# Shield_Amir_EDO_V_0_2.net
KiCad netlist of a schematic drawn in EasyEDA
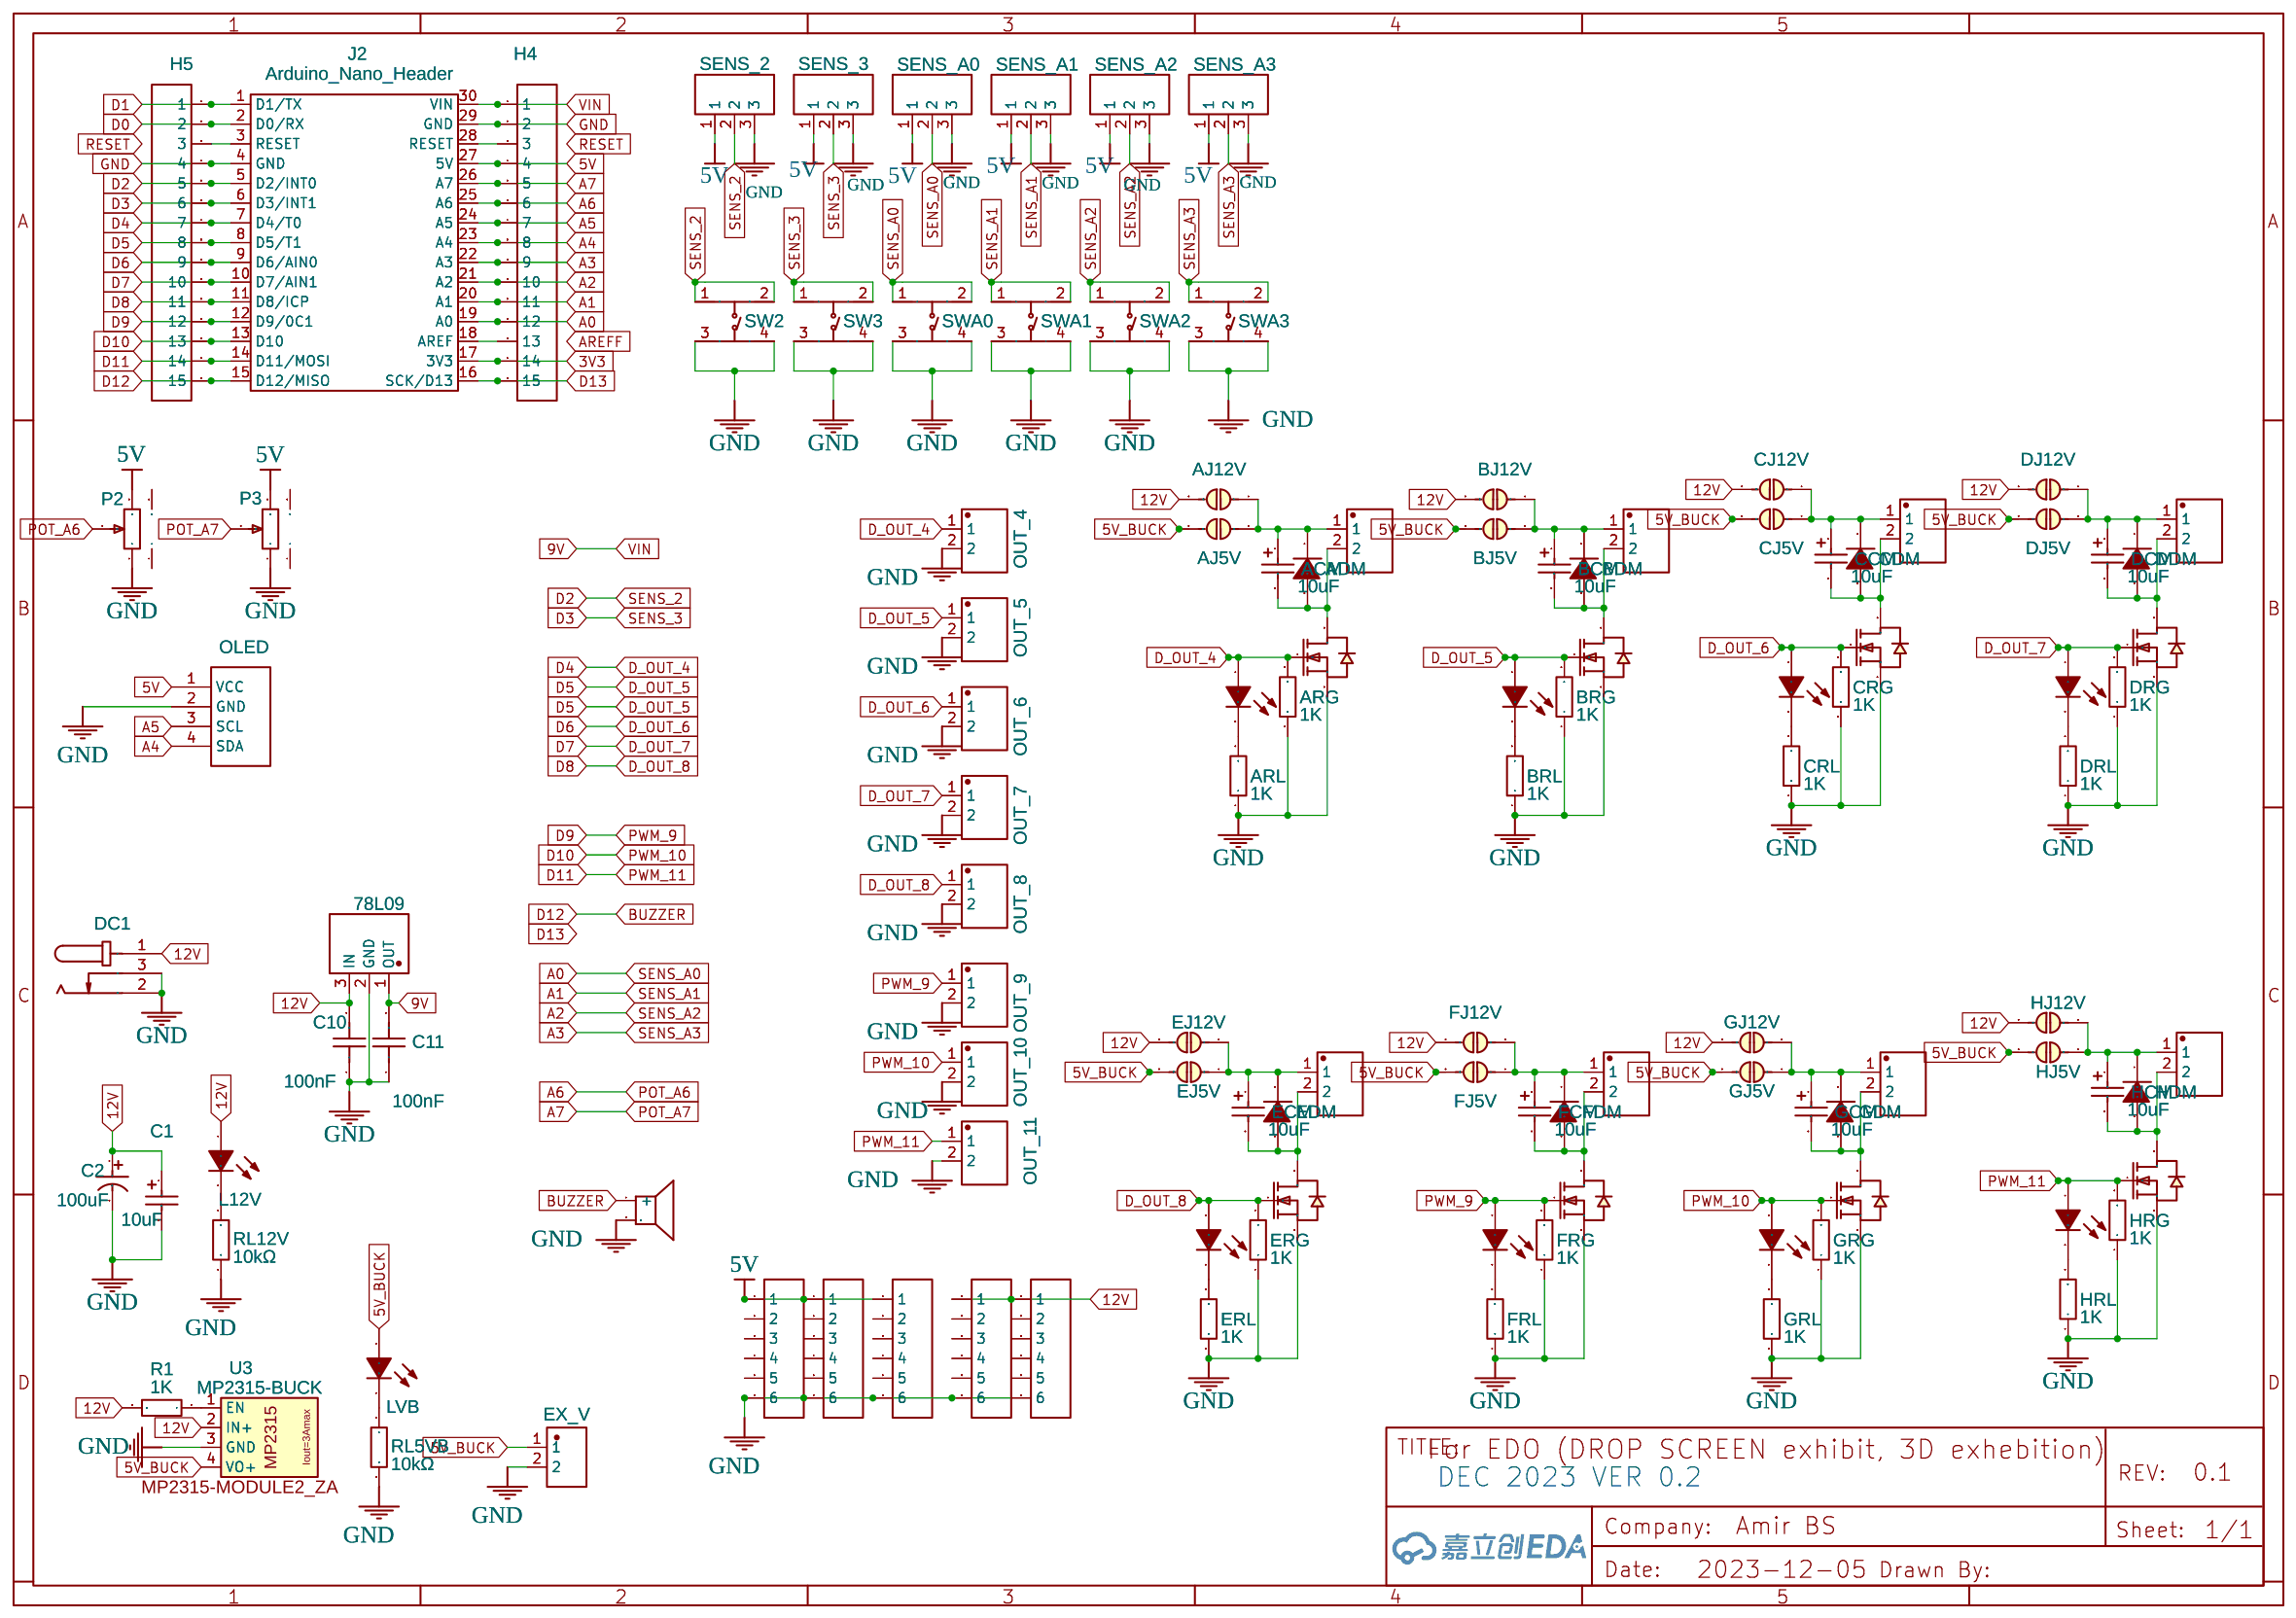
[diagram p0: schematic sheet]

(export (version "E")
  (design (tool "Eeschema 10.0.6"))
  (components
    (comp (ref "ACM")
      (value "10uF")
      (fields (field (name "Manufacturer Part") "TAJA106K016RNJ") (field (name "Manufacturer") "Kyocera AVX"))
      (libsource (lib "") (part "TAJA106K016RNJ_5"))
    )
    (comp (ref "ACON")
      (value "KF2510-2A")
      (fields (field (name "BOM_Supplier Part") "C27543"))
      (libsource (lib "") (part "KF2510-2A_6"))
    )
    (comp (ref "ADM")
      (value "1N4007")
      (fields (field (name "BOM_Manufacturer Part") "1N4007F") (field (name "BOM_Supplier Part") "C110856"))
      (libsource (lib "") (part "1N4007F_5"))
    )
    (comp (ref "AJ5V") (value "JUMPER-SMT_2") (libsource (lib "") (part "JUMPER-SMT_2_7")))
    (comp (ref "AJ12V") (value "JUMPER-SMT_2") (libsource (lib "") (part "JUMPER-SMT_2_3")))
    (comp (ref "ALD")
      (value "LED")
      (fields
        (field (name "BOM_Manufacturer Part") "19-217/BHC-ZL1M2RY/3T")
        (field (name "BOM_Supplier Part") "C72041")
      )
      (libsource (lib "") (part "19-217/BHC-ZL1M2RY/3T_4"))
    )
    (comp (ref "AQ")
      (value "Q")
      (fields (field (name "BOM_Manufacturer Part") "AO3400") (field (name "BOM_Supplier Part") "C5224189"))
      (libsource (lib "") (part "JSM2302_1"))
    )
    (comp (ref "ARG")
      (value "1K")
      (fields
        (field (name "BOM_Manufacturer Part") "0603WAF1001T5E")
        (field (name "BOM_Supplier Part") "C21190")
      )
      (libsource (lib "") (part "0603WAF1001T5E_11"))
    )
    (comp (ref "ARL")
      (value "1K")
      (fields
        (field (name "BOM_Manufacturer Part") "0603WAF1001T5E")
        (field (name "BOM_Supplier Part") "C21190")
      )
      (libsource (lib "") (part "0603WAF1001T5E_5"))
    )
    (comp (ref "BCM")
      (value "10uF")
      (fields (field (name "Manufacturer Part") "TAJA106K016RNJ") (field (name "Manufacturer") "Kyocera AVX"))
      (libsource (lib "") (part "TAJA106K016RNJ_7"))
    )
    (comp (ref "BCON")
      (value "KF2510-2A")
      (fields (field (name "BOM_Supplier Part") "C27543"))
      (libsource (lib "") (part "KF2510-2A_4"))
    )
    (comp (ref "BDM")
      (value "1N4007")
      (fields (field (name "BOM_Manufacturer Part") "1N4007F") (field (name "BOM_Supplier Part") "C110856"))
      (libsource (lib "") (part "1N4007F_7"))
    )
    (comp (ref "BJ5V") (value "JUMPER-SMT_2") (libsource (lib "") (part "JUMPER-SMT_2_13")))
    (comp (ref "BJ12V") (value "JUMPER-SMT_2") (libsource (lib "") (part "JUMPER-SMT_2_6")))
    (comp (ref "BLD")
      (value "LED")
      (fields
        (field (name "BOM_Manufacturer Part") "19-217/BHC-ZL1M2RY/3T")
        (field (name "BOM_Supplier Part") "C72041")
      )
      (libsource (lib "") (part "19-217/BHC-ZL1M2RY/3T_7"))
    )
    (comp (ref "BQ")
      (value "Q")
      (fields (field (name "BOM_Manufacturer Part") "AO3400") (field (name "BOM_Supplier Part") "C5224189"))
      (libsource (lib "") (part "JSM2302_4"))
    )
    (comp (ref "BRG")
      (value "1K")
      (fields
        (field (name "BOM_Manufacturer Part") "0603WAF1001T5E")
        (field (name "BOM_Supplier Part") "C21190")
      )
      (libsource (lib "") (part "0603WAF1001T5E_7"))
    )
    (comp (ref "BRL")
      (value "1K")
      (fields
        (field (name "BOM_Manufacturer Part") "0603WAF1001T5E")
        (field (name "BOM_Supplier Part") "C21190")
      )
      (libsource (lib "") (part "0603WAF1001T5E_3"))
    )
    (comp (ref "BUZZER1")
      (value "BUZZER-12X9")
      (fields (field (name "Manufacturer Part") "buzzer-12X9"))
      (libsource (lib "") (part "BUZZER-12X9"))
    )
    (comp (ref "C1")
      (value "10uF")
      (fields (field (name "Manufacturer Part") "TAJA106K016RNJ") (field (name "Manufacturer") "Kyocera AVX"))
      (libsource (lib "") (part "TAJA106K016RNJ_4"))
    )
    (comp (ref "C2")
      (value "100uF")
      (fields
        (field (name "Manufacturer Part") "KM107M035E11RR0VH2FP0")
        (field (name "Manufacturer") "CX(承兴)")
      )
      (libsource (lib "") (part "100uF 35V 6.3*11"))
    )
    (comp (ref "C10")
      (value "100nF")
      (fields
        (field (name "Manufacturer Part") "CC0603KRX7R9BB104")
        (field (name "Manufacturer") "YAGEO(国巨)")
      )
      (libsource (lib "") (part "CC0603KRX7R9BB104"))
    )
    (comp (ref "C11")
      (value "100nF")
      (fields
        (field (name "Manufacturer Part") "CC0603KRX7R9BB104")
        (field (name "Manufacturer") "YAGEO(国巨)")
      )
      (libsource (lib "") (part "CC0603KRX7R9BB104"))
    )
    (comp (ref "CCM")
      (value "10uF")
      (fields (field (name "Manufacturer Part") "TAJA106K016RNJ") (field (name "Manufacturer") "Kyocera AVX"))
      (libsource (lib "") (part "TAJA106K016RNJ_2"))
    )
    (comp (ref "CCON")
      (value "KF2510-2A")
      (fields (field (name "BOM_Supplier Part") "C27543"))
      (libsource (lib "") (part "KF2510-2A_3"))
    )
    (comp (ref "CDM")
      (value "1N4007")
      (fields (field (name "BOM_Manufacturer Part") "1N4007F") (field (name "BOM_Supplier Part") "C110856"))
      (libsource (lib "") (part "1N4007F_1"))
    )
    (comp (ref "CJ5V") (value "JUMPER-SMT_2") (libsource (lib "") (part "JUMPER-SMT_2_9")))
    (comp (ref "CJ12V") (value "JUMPER-SMT_2") (libsource (lib "") (part "JUMPER-SMT_2_2")))
    (comp (ref "CLD")
      (value "LED")
      (fields
        (field (name "BOM_Manufacturer Part") "19-217/BHC-ZL1M2RY/3T")
        (field (name "BOM_Supplier Part") "C72041")
      )
      (libsource (lib "") (part "19-217/BHC-ZL1M2RY/3T"))
    )
    (comp (ref "CQ")
      (value "Q")
      (fields (field (name "BOM_Manufacturer Part") "AO3400") (field (name "BOM_Supplier Part") "C5224189"))
      (libsource (lib "") (part "JSM2302_7"))
    )
    (comp (ref "CRG")
      (value "1K")
      (fields
        (field (name "BOM_Manufacturer Part") "0603WAF1001T5E")
        (field (name "BOM_Supplier Part") "C21190")
      )
      (libsource (lib "") (part "0603WAF1001T5E_6"))
    )
    (comp (ref "CRL")
      (value "1K")
      (fields
        (field (name "BOM_Manufacturer Part") "0603WAF1001T5E")
        (field (name "BOM_Supplier Part") "C21190")
      )
      (libsource (lib "") (part "0603WAF1001T5E_16"))
    )
    (comp (ref "DC1")
      (value "DC")
      (fields
        (field (name "BOM_Manufacturer Part") "DC005-2.0MM")
        (field (name "BOM_Supplier Part") "C111567")
      )
      (libsource (lib "") (part "DC005-2.0MM"))
    )
    (comp (ref "DCM")
      (value "10uF")
      (fields (field (name "Manufacturer Part") "TAJA106K016RNJ") (field (name "Manufacturer") "Kyocera AVX"))
      (libsource (lib "") (part "TAJA106K016RNJ_1"))
    )
    (comp (ref "DCON")
      (value "KF2510-2A")
      (fields (field (name "BOM_Supplier Part") "C27543"))
      (libsource (lib "") (part "KF2510-2A"))
    )
    (comp (ref "DDM")
      (value "1N4007")
      (fields (field (name "BOM_Manufacturer Part") "1N4007F") (field (name "BOM_Supplier Part") "C110856"))
      (libsource (lib "") (part "1N4007F_2"))
    )
    (comp (ref "DJ5V") (value "JUMPER-SMT_2") (libsource (lib "") (part "JUMPER-SMT_2_12")))
    (comp (ref "DJ12V") (value "JUMPER-SMT_2") (libsource (lib "") (part "JUMPER-SMT_2_14")))
    (comp (ref "DLD")
      (value "LED")
      (fields
        (field (name "BOM_Manufacturer Part") "19-217/BHC-ZL1M2RY/3T")
        (field (name "BOM_Supplier Part") "C72041")
      )
      (libsource (lib "") (part "19-217/BHC-ZL1M2RY/3T_1"))
    )
    (comp (ref "DQ")
      (value "Q")
      (fields (field (name "BOM_Manufacturer Part") "AO3400") (field (name "BOM_Supplier Part") "C5224189"))
      (libsource (lib "") (part "JSM2302_2"))
    )
    (comp (ref "DRG")
      (value "1K")
      (fields
        (field (name "BOM_Manufacturer Part") "0603WAF1001T5E")
        (field (name "BOM_Supplier Part") "C21190")
      )
      (libsource (lib "") (part "0603WAF1001T5E_8"))
    )
    (comp (ref "DRL")
      (value "1K")
      (fields
        (field (name "BOM_Manufacturer Part") "0603WAF1001T5E")
        (field (name "BOM_Supplier Part") "C21190")
      )
      (libsource (lib "") (part "0603WAF1001T5E_9"))
    )
    (comp (ref "ECM")
      (value "10uF")
      (fields (field (name "Manufacturer Part") "TAJA106K016RNJ") (field (name "Manufacturer") "Kyocera AVX"))
      (libsource (lib "") (part "TAJA106K016RNJ_6"))
    )
    (comp (ref "ECON")
      (value "KF2510-2A")
      (fields (field (name "BOM_Supplier Part") "C27543"))
      (libsource (lib "") (part "KF2510-2A_8"))
    )
    (comp (ref "EDM")
      (value "1N4007")
      (fields (field (name "BOM_Manufacturer Part") "1N4007F") (field (name "BOM_Supplier Part") "C110856"))
      (libsource (lib "") (part "1N4007F"))
    )
    (comp (ref "EJ5V") (value "JUMPER-SMT_2") (libsource (lib "") (part "JUMPER-SMT_2_11")))
    (comp (ref "EJ12V") (value "JUMPER-SMT_2") (libsource (lib "") (part "JUMPER-SMT_2_1")))
    (comp (ref "ELD")
      (value "LED")
      (fields
        (field (name "BOM_Manufacturer Part") "19-217/BHC-ZL1M2RY/3T")
        (field (name "BOM_Supplier Part") "C72041")
      )
      (libsource (lib "") (part "19-217/BHC-ZL1M2RY/3T_3"))
    )
    (comp (ref "EQ")
      (value "Q")
      (fields (field (name "BOM_Manufacturer Part") "AO3400") (field (name "BOM_Supplier Part") "C5224189"))
      (libsource (lib "") (part "JSM2302_6"))
    )
    (comp (ref "ERG")
      (value "1K")
      (fields
        (field (name "BOM_Manufacturer Part") "0603WAF1001T5E")
        (field (name "BOM_Supplier Part") "C21190")
      )
      (libsource (lib "") (part "0603WAF1001T5E_13"))
    )
    (comp (ref "ERL")
      (value "1K")
      (fields
        (field (name "BOM_Manufacturer Part") "0603WAF1001T5E")
        (field (name "BOM_Supplier Part") "C21190")
      )
      (libsource (lib "") (part "0603WAF1001T5E_1"))
    )
    (comp (ref "EX_V")
      (value "EX_V")
      (fields
        (field (name "Manufacturer Part") "WJ306V-5.0-2P-14-00A")
        (field (name "Manufacturer") "KANGNEX(康奈克斯电气)")
      )
      (libsource (lib "") (part "WJ306V-5.0-2P-14-00A"))
    )
    (comp (ref "FCM")
      (value "10uF")
      (fields (field (name "Manufacturer Part") "TAJA106K016RNJ") (field (name "Manufacturer") "Kyocera AVX"))
      (libsource (lib "") (part "TAJA106K016RNJ"))
    )
    (comp (ref "FCON")
      (value "KF2510-2A")
      (fields (field (name "BOM_Supplier Part") "C27543"))
      (libsource (lib "") (part "KF2510-2A_7"))
    )
    (comp (ref "FDM")
      (value "1N4007")
      (fields (field (name "BOM_Manufacturer Part") "1N4007F") (field (name "BOM_Supplier Part") "C110856"))
      (libsource (lib "") (part "1N4007F_6"))
    )
    (comp (ref "FJ5V") (value "JUMPER-SMT_2") (libsource (lib "") (part "JUMPER-SMT_2_15")))
    (comp (ref "FJ12V") (value "JUMPER-SMT_2") (libsource (lib "") (part "JUMPER-SMT_2_5")))
    (comp (ref "FLD")
      (value "LED")
      (fields
        (field (name "BOM_Manufacturer Part") "19-217/BHC-ZL1M2RY/3T")
        (field (name "BOM_Supplier Part") "C72041")
      )
      (libsource (lib "") (part "19-217/BHC-ZL1M2RY/3T_9"))
    )
    (comp (ref "FQ")
      (value "Q")
      (fields (field (name "BOM_Manufacturer Part") "AO3400") (field (name "BOM_Supplier Part") "C5224189"))
      (libsource (lib "") (part "JSM2302"))
    )
    (comp (ref "FRG")
      (value "1K")
      (fields
        (field (name "BOM_Manufacturer Part") "0603WAF1001T5E")
        (field (name "BOM_Supplier Part") "C21190")
      )
      (libsource (lib "") (part "0603WAF1001T5E_15"))
    )
    (comp (ref "FRL")
      (value "1K")
      (fields
        (field (name "BOM_Manufacturer Part") "0603WAF1001T5E")
        (field (name "BOM_Supplier Part") "C21190")
      )
      (libsource (lib "") (part "0603WAF1001T5E"))
    )
    (comp (ref "GCM")
      (value "10uF")
      (fields (field (name "Manufacturer Part") "TAJA106K016RNJ") (field (name "Manufacturer") "Kyocera AVX"))
      (libsource (lib "") (part "TAJA106K016RNJ_8"))
    )
    (comp (ref "GCON")
      (value "KF2510-2A")
      (fields (field (name "BOM_Supplier Part") "C27543"))
      (libsource (lib "") (part "KF2510-2A_2"))
    )
    (comp (ref "GDM")
      (value "1N4007")
      (fields (field (name "BOM_Manufacturer Part") "1N4007F") (field (name "BOM_Supplier Part") "C110856"))
      (libsource (lib "") (part "1N4007F_3"))
    )
    (comp (ref "GJ5V") (value "JUMPER-SMT_2") (libsource (lib "") (part "JUMPER-SMT_2_10")))
    (comp (ref "GJ12V") (value "JUMPER-SMT_2") (libsource (lib "") (part "JUMPER-SMT_2_8")))
    (comp (ref "GLD")
      (value "LED")
      (fields
        (field (name "BOM_Manufacturer Part") "19-217/BHC-ZL1M2RY/3T")
        (field (name "BOM_Supplier Part") "C72041")
      )
      (libsource (lib "") (part "19-217/BHC-ZL1M2RY/3T_6"))
    )
    (comp (ref "GQ")
      (value "Q")
      (fields (field (name "BOM_Manufacturer Part") "AO3400") (field (name "BOM_Supplier Part") "C5224189"))
      (libsource (lib "") (part "JSM2302_5"))
    )
    (comp (ref "GRG")
      (value "1K")
      (fields
        (field (name "BOM_Manufacturer Part") "0603WAF1001T5E")
        (field (name "BOM_Supplier Part") "C21190")
      )
      (libsource (lib "") (part "0603WAF1001T5E_2"))
    )
    (comp (ref "GRL")
      (value "1K")
      (fields
        (field (name "BOM_Manufacturer Part") "0603WAF1001T5E")
        (field (name "BOM_Supplier Part") "C21190")
      )
      (libsource (lib "") (part "0603WAF1001T5E_12"))
    )
    (comp (ref "H1")
      (value "HDR-F-2.54_1x6")
      (fields (field (name "BOM_Supplier Part") "C40877"))
      (libsource (lib "") (part "HDR-F-2.54_1x6"))
    )
    (comp (ref "H2")
      (value "HDR-F-2.54_1x6")
      (fields (field (name "BOM_Supplier Part") "C40877"))
      (libsource (lib "") (part "HDR-F-2.54_1x6"))
    )
    (comp (ref "H3")
      (value "HDR-F-2.54_1x6")
      (fields (field (name "BOM_Supplier Part") "C40877"))
      (libsource (lib "") (part "HDR-F-2.54_1x6"))
    )
    (comp (ref "H4")
      (value "HDR-F-2.54_1x15")
      (fields (field (name "BOM_Supplier Part") "C124408"))
      (libsource (lib "") (part "HDR-F-2.54_1x15_1"))
    )
    (comp (ref "H5")
      (value "HDR-F-2.54_1x15")
      (fields (field (name "BOM_Supplier Part") "C124408"))
      (libsource (lib "") (part "HDR-F-2.54_1x15"))
    )
    (comp (ref "H6")
      (value "HDR-F-2.54_1x6")
      (fields (field (name "BOM_Supplier Part") "C40877"))
      (libsource (lib "") (part "HDR-F-2.54_1x6"))
    )
    (comp (ref "H11")
      (value "HDR-F-2.54_1x6")
      (fields (field (name "BOM_Supplier Part") "C40877"))
      (libsource (lib "") (part "HDR-F-2.54_1x6"))
    )
    (comp (ref "HCM")
      (value "10uF")
      (fields (field (name "Manufacturer Part") "TAJA106K016RNJ") (field (name "Manufacturer") "Kyocera AVX"))
      (libsource (lib "") (part "TAJA106K016RNJ_3"))
    )
    (comp (ref "HCON")
      (value "KF2510-2A")
      (fields (field (name "BOM_Supplier Part") "C27543"))
      (libsource (lib "") (part "KF2510-2A_5"))
    )
    (comp (ref "HDM")
      (value "1N4007")
      (fields (field (name "BOM_Manufacturer Part") "1N4007F") (field (name "BOM_Supplier Part") "C110856"))
      (libsource (lib "") (part "1N4007F_4"))
    )
    (comp (ref "HJ5V") (value "JUMPER-SMT_2") (libsource (lib "") (part "JUMPER-SMT_2")))
    (comp (ref "HJ12V") (value "JUMPER-SMT_2") (libsource (lib "") (part "JUMPER-SMT_2_4")))
    (comp (ref "HLD")
      (value "LED")
      (fields
        (field (name "BOM_Manufacturer Part") "19-217/BHC-ZL1M2RY/3T")
        (field (name "BOM_Supplier Part") "C72041")
      )
      (libsource (lib "") (part "19-217/BHC-ZL1M2RY/3T_2"))
    )
    (comp (ref "HQ")
      (value "Q")
      (fields (field (name "BOM_Manufacturer Part") "AO3400") (field (name "BOM_Supplier Part") "C5224189"))
      (libsource (lib "") (part "JSM2302_3"))
    )
    (comp (ref "HRG")
      (value "1K")
      (fields
        (field (name "BOM_Manufacturer Part") "0603WAF1001T5E")
        (field (name "BOM_Supplier Part") "C21190")
      )
      (libsource (lib "") (part "0603WAF1001T5E_4"))
    )
    (comp (ref "HRL")
      (value "1K")
      (fields
        (field (name "BOM_Manufacturer Part") "0603WAF1001T5E")
        (field (name "BOM_Supplier Part") "C21190")
      )
      (libsource (lib "") (part "0603WAF1001T5E_14"))
    )
    (comp (ref "J2") (value "Arduino_Nano_Header") (libsource (lib "") (part "Arduino_Nano_Header")))
    (comp (ref "L12V")
      (value "LED")
      (fields
        (field (name "BOM_Manufacturer Part") "19-217/BHC-ZL1M2RY/3T")
        (field (name "BOM_Supplier Part") "C72041")
      )
      (libsource (lib "") (part "19-217/BHC-ZL1M2RY/3T_5"))
    )
    (comp (ref "LVB")
      (value "LED")
      (fields
        (field (name "BOM_Manufacturer Part") "19-217/BHC-ZL1M2RY/3T")
        (field (name "BOM_Supplier Part") "C72041")
      )
      (libsource (lib "") (part "19-217/BHC-ZL1M2RY/3T_8"))
    )
    (comp (ref "OLED")
      (value "1.3 inch OLED SSH1106 I2C 128x64 copy")
      (libsource (lib "") (part "1.3 inch OLED SSH1106 I2C 128x64 copy"))
    )
    (comp (ref "OUT_4")
      (value "KF2510-2A")
      (fields (field (name "BOM_Supplier Part") "C27543"))
      (libsource (lib "") (part "KF2510-2A_1"))
    )
    (comp (ref "OUT_5")
      (value "KF2510-2A")
      (fields (field (name "BOM_Supplier Part") "C27543"))
      (libsource (lib "") (part "KF2510-2A_1"))
    )
    (comp (ref "OUT_6")
      (value "KF2510-2A")
      (fields (field (name "BOM_Supplier Part") "C27543"))
      (libsource (lib "") (part "KF2510-2A_1"))
    )
    (comp (ref "OUT_7")
      (value "KF2510-2A")
      (fields (field (name "BOM_Supplier Part") "C27543"))
      (libsource (lib "") (part "KF2510-2A_1"))
    )
    (comp (ref "OUT_8")
      (value "KF2510-2A")
      (fields (field (name "BOM_Supplier Part") "C27543"))
      (libsource (lib "") (part "KF2510-2A_1"))
    )
    (comp (ref "OUT_9")
      (value "KF2510-2A")
      (fields (field (name "BOM_Supplier Part") "C27543"))
      (libsource (lib "") (part "KF2510-2A_1"))
    )
    (comp (ref "OUT_10")
      (value "KF2510-2A")
      (fields (field (name "BOM_Supplier Part") "C27543"))
      (libsource (lib "") (part "KF2510-2A_1"))
    )
    (comp (ref "OUT_11")
      (value "KF2510-2A")
      (fields (field (name "BOM_Supplier Part") "C27543"))
      (libsource (lib "") (part "KF2510-2A_1"))
    )
    (comp (ref "P2")
      (value "长柄旋转电位器")
      (fields (field (name "BOM_Supplier Part") "C2874842"))
      (libsource (lib "") (part "长柄旋转电位器"))
    )
    (comp (ref "P3")
      (value "长柄旋转电位器")
      (fields (field (name "BOM_Supplier Part") "C2874842"))
      (libsource (lib "") (part "长柄旋转电位器"))
    )
    (comp (ref "R1")
      (value "1K")
      (fields
        (field (name "BOM_Manufacturer Part") "0603WAF1001T5E")
        (field (name "BOM_Supplier Part") "C21190")
      )
      (libsource (lib "") (part "0603WAF1001T5E_10"))
    )
    (comp (ref "RL5VB")
      (value "10kΩ")
      (fields
        (field (name "BOM_Manufacturer Part") "0603WAF1002T5E")
        (field (name "BOM_Supplier Part") "C25804")
      )
      (libsource (lib "") (part "0603WAF1002T5E"))
    )
    (comp (ref "RL12V")
      (value "10kΩ")
      (fields
        (field (name "BOM_Manufacturer Part") "0603WAF1002T5E")
        (field (name "BOM_Supplier Part") "C25804")
      )
      (libsource (lib "") (part "0603WAF1002T5E_1"))
    )
    (comp (ref "SENS_2")
      (value "FK2510")
      (fields (field (name "Manufacturer Part") "2510-3A") (field (name "Manufacturer") "BOOMELE(博穆精密)"))
      (libsource (lib "") (part "kf2510_3A_1"))
    )
    (comp (ref "SENS_3")
      (value "FK2510")
      (fields (field (name "Manufacturer Part") "2510-3A") (field (name "Manufacturer") "BOOMELE(博穆精密)"))
      (libsource (lib "") (part "kf2510_3A_1"))
    )
    (comp (ref "SENS_A0")
      (value "FK2510")
      (fields (field (name "Manufacturer Part") "2510-3A") (field (name "Manufacturer") "BOOMELE(博穆精密)"))
      (libsource (lib "") (part "kf2510_3A"))
    )
    (comp (ref "SENS_A1")
      (value "FK2510")
      (fields (field (name "Manufacturer Part") "2510-3A") (field (name "Manufacturer") "BOOMELE(博穆精密)"))
      (libsource (lib "") (part "kf2510_3A"))
    )
    (comp (ref "SENS_A2")
      (value "FK2510")
      (fields (field (name "Manufacturer Part") "2510-3A") (field (name "Manufacturer") "BOOMELE(博穆精密)"))
      (libsource (lib "") (part "kf2510_3A"))
    )
    (comp (ref "SENS_A3")
      (value "FK2510")
      (fields (field (name "Manufacturer Part") "2510-3A") (field (name "Manufacturer") "BOOMELE(博穆精密)"))
      (libsource (lib "") (part "kf2510_3A"))
    )
    (comp (ref "SW2")
      (value "TC-6610-7-160G")
      (fields (field (name "Manufacturer") "HCTL(华灿天禄)"))
      (libsource (lib "") (part "TC-6610-7-160G_1"))
    )
    (comp (ref "SW3")
      (value "TC-6610-7-160G")
      (fields (field (name "Manufacturer") "HCTL(华灿天禄)"))
      (libsource (lib "") (part "TC-6610-7-160G_1"))
    )
    (comp (ref "SWA0")
      (value "TC-6610-7-160G")
      (fields (field (name "Manufacturer") "HCTL(华灿天禄)"))
      (libsource (lib "") (part "TC-6610-7-160G"))
    )
    (comp (ref "SWA1")
      (value "TC-6610-7-160G")
      (fields (field (name "Manufacturer") "HCTL(华灿天禄)"))
      (libsource (lib "") (part "TC-6610-7-160G"))
    )
    (comp (ref "SWA2")
      (value "TC-6610-7-160G")
      (fields (field (name "Manufacturer") "HCTL(华灿天禄)"))
      (libsource (lib "") (part "TC-6610-7-160G"))
    )
    (comp (ref "SWA3")
      (value "TC-6610-7-160G")
      (fields (field (name "Manufacturer") "HCTL(华灿天禄)"))
      (libsource (lib "") (part "TC-6610-7-160G"))
    )
    (comp (ref "U3") (value "MP2315-BUCK") (libsource (lib "") (part "MP2315-BUCK")))
    (comp (ref "U5")
      (value "78L09")
      (fields (field (name "Manufacturer Part") "78L09U 78L09") (field (name "Manufacturer") "CBI(创基)"))
      (libsource (lib "") (part "78L09U 78L09"))
    )
  )
  (nets
    (net (code "1") (name "3V3") (class "Default")
      (node (ref "H4") (pin "14") (pinfunction "14_14") (pintype "unspecified"))
      (node (ref "J2") (pin "17") (pinfunction "3V3_17") (pintype "unspecified"))
    )
    (net (code "2") (name "5V") (class "Default")
      (node (ref "H1") (pin "1") (pinfunction "1_1") (pintype "input"))
      (node (ref "H2") (pin "1") (pinfunction "1_1") (pintype "input"))
      (node (ref "H3") (pin "1") (pinfunction "1_1") (pintype "input"))
      (node (ref "H4") (pin "4") (pinfunction "4_4") (pintype "unspecified"))
      (node (ref "J2") (pin "27") (pinfunction "5V_27") (pintype "unspecified"))
      (node (ref "OLED") (pin "1") (pinfunction "VCC_1") (pintype "passive"))
      (node (ref "P2") (pin "3") (pinfunction "3_3") (pintype "input"))
      (node (ref "P3") (pin "3") (pinfunction "3_3") (pintype "input"))
      (node (ref "SENS_2") (pin "1") (pinfunction "1_1") (pintype "unspecified"))
      (node (ref "SENS_3") (pin "1") (pinfunction "1_1") (pintype "unspecified"))
      (node (ref "SENS_A0") (pin "1") (pinfunction "1_1") (pintype "unspecified"))
      (node (ref "SENS_A1") (pin "1") (pinfunction "1_1") (pintype "unspecified"))
      (node (ref "SENS_A2") (pin "1") (pinfunction "1_1") (pintype "unspecified"))
      (node (ref "SENS_A3") (pin "1") (pinfunction "1_1") (pintype "unspecified"))
    )
    (net (code "3") (name "5V_BUCK") (class "Default")
      (node (ref "AJ5V") (pin "2") (pinfunction "2_2") (pintype "bidirectional"))
      (node (ref "BJ5V") (pin "2") (pinfunction "2_2") (pintype "bidirectional"))
      (node (ref "CJ5V") (pin "2") (pinfunction "2_2") (pintype "bidirectional"))
      (node (ref "DJ5V") (pin "2") (pinfunction "2_2") (pintype "bidirectional"))
      (node (ref "EJ5V") (pin "2") (pinfunction "2_2") (pintype "bidirectional"))
      (node (ref "EX_V") (pin "1") (pinfunction "1_1") (pintype "unspecified"))
      (node (ref "FJ5V") (pin "2") (pinfunction "2_2") (pintype "bidirectional"))
      (node (ref "GJ5V") (pin "2") (pinfunction "2_2") (pintype "bidirectional"))
      (node (ref "HJ5V") (pin "2") (pinfunction "2_2") (pintype "bidirectional"))
      (node (ref "LVB") (pin "1") (pinfunction "A_1") (pintype "input"))
      (node (ref "U3") (pin "4") (pinfunction "VO+_4") (pintype "unspecified"))
    )
    (net (code "4") (name "9V") (class "Default")
      (node (ref "C11") (pin "2") (pinfunction "2_2") (pintype "unspecified"))
      (node (ref "H4") (pin "1") (pinfunction "1_1") (pintype "unspecified"))
      (node (ref "J2") (pin "30") (pinfunction "VIN_30") (pintype "unspecified"))
      (node (ref "U5") (pin "1") (pinfunction "OUT_1") (pintype "unspecified"))
    )
    (net (code "5") (name "12V") (class "Default")
      (node (ref "AJ12V") (pin "2") (pinfunction "2_2") (pintype "bidirectional"))
      (node (ref "BJ12V") (pin "2") (pinfunction "2_2") (pintype "bidirectional"))
      (node (ref "C1") (pin "1") (pinfunction "1_1") (pintype "input"))
      (node (ref "C10") (pin "2") (pinfunction "2_2") (pintype "unspecified"))
      (node (ref "C2") (pin "1") (pinfunction "1_1") (pintype "input"))
      (node (ref "CJ12V") (pin "2") (pinfunction "2_2") (pintype "bidirectional"))
      (node (ref "DC1") (pin "1") (pinfunction "1_1") (pintype "unspecified"))
      (node (ref "DJ12V") (pin "2") (pinfunction "2_2") (pintype "bidirectional"))
      (node (ref "EJ12V") (pin "2") (pinfunction "2_2") (pintype "bidirectional"))
      (node (ref "FJ12V") (pin "2") (pinfunction "2_2") (pintype "bidirectional"))
      (node (ref "GJ12V") (pin "2") (pinfunction "2_2") (pintype "bidirectional"))
      (node (ref "H11") (pin "1") (pinfunction "1_1") (pintype "input"))
      (node (ref "H6") (pin "1") (pinfunction "1_1") (pintype "input"))
      (node (ref "HJ12V") (pin "2") (pinfunction "2_2") (pintype "bidirectional"))
      (node (ref "L12V") (pin "1") (pinfunction "A_1") (pintype "input"))
      (node (ref "R1") (pin "2") (pinfunction "2_2") (pintype "input"))
      (node (ref "U3") (pin "2") (pinfunction "IN+_2") (pintype "unspecified"))
      (node (ref "U5") (pin "3") (pinfunction "IN_3") (pintype "unspecified"))
    )
    (net (code "6") (name "A0") (class "Default")
      (node (ref "H4") (pin "12") (pinfunction "12_12") (pintype "unspecified"))
      (node (ref "J2") (pin "19") (pinfunction "A0_19") (pintype "unspecified"))
      (node (ref "SENS_A0") (pin "2") (pinfunction "2_2") (pintype "unspecified"))
      (node (ref "SWA0") (pin "1") (pinfunction "1_1") (pintype "unspecified"))
      (node (ref "SWA0") (pin "2") (pinfunction "2_2") (pintype "unspecified"))
    )
    (net (code "7") (name "A1") (class "Default")
      (node (ref "H4") (pin "11") (pinfunction "11_11") (pintype "unspecified"))
      (node (ref "J2") (pin "20") (pinfunction "A1_20") (pintype "unspecified"))
      (node (ref "SENS_A1") (pin "2") (pinfunction "2_2") (pintype "unspecified"))
      (node (ref "SWA1") (pin "1") (pinfunction "1_1") (pintype "unspecified"))
      (node (ref "SWA1") (pin "2") (pinfunction "2_2") (pintype "unspecified"))
    )
    (net (code "8") (name "A2") (class "Default")
      (node (ref "H4") (pin "10") (pinfunction "10_10") (pintype "unspecified"))
      (node (ref "J2") (pin "21") (pinfunction "A2_21") (pintype "unspecified"))
      (node (ref "SENS_A2") (pin "2") (pinfunction "2_2") (pintype "unspecified"))
      (node (ref "SWA2") (pin "1") (pinfunction "1_1") (pintype "unspecified"))
      (node (ref "SWA2") (pin "2") (pinfunction "2_2") (pintype "unspecified"))
    )
    (net (code "9") (name "A3") (class "Default")
      (node (ref "H4") (pin "9") (pinfunction "9_9") (pintype "unspecified"))
      (node (ref "J2") (pin "22") (pinfunction "A3_22") (pintype "unspecified"))
      (node (ref "SENS_A3") (pin "2") (pinfunction "2_2") (pintype "unspecified"))
      (node (ref "SWA3") (pin "1") (pinfunction "1_1") (pintype "unspecified"))
      (node (ref "SWA3") (pin "2") (pinfunction "2_2") (pintype "unspecified"))
    )
    (net (code "10") (name "A4") (class "Default")
      (node (ref "H4") (pin "8") (pinfunction "8_8") (pintype "unspecified"))
      (node (ref "J2") (pin "23") (pinfunction "A4_23") (pintype "unspecified"))
      (node (ref "OLED") (pin "4") (pinfunction "SDA_4") (pintype "bidirectional"))
    )
    (net (code "11") (name "A5") (class "Default")
      (node (ref "H4") (pin "7") (pinfunction "7_7") (pintype "unspecified"))
      (node (ref "J2") (pin "24") (pinfunction "A5_24") (pintype "unspecified"))
      (node (ref "OLED") (pin "3") (pinfunction "SCL_3") (pintype "bidirectional"))
    )
    (net (code "12") (name "A6") (class "Default")
      (node (ref "H4") (pin "6") (pinfunction "6_6") (pintype "unspecified"))
      (node (ref "J2") (pin "25") (pinfunction "A6_25") (pintype "unspecified"))
      (node (ref "P2") (pin "2") (pinfunction "2_2") (pintype "input"))
    )
    (net (code "13") (name "A7") (class "Default")
      (node (ref "H4") (pin "5") (pinfunction "5_5") (pintype "unspecified"))
      (node (ref "J2") (pin "26") (pinfunction "A7_26") (pintype "unspecified"))
      (node (ref "P3") (pin "2") (pinfunction "2_2") (pintype "input"))
    )
    (net (code "15") (name "BUZZER") (class "Default")
      (node (ref "BUZZER1") (pin "1") (pinfunction "+_1") (pintype "unspecified"))
      (node (ref "H5") (pin "15") (pinfunction "15_15") (pintype "unspecified"))
      (node (ref "J2") (pin "15") (pinfunction "D12/MISO_15") (pintype "unspecified"))
    )
    (net (code "16") (name "D0") (class "Default")
      (node (ref "H5") (pin "2") (pinfunction "2_2") (pintype "unspecified"))
      (node (ref "J2") (pin "2") (pinfunction "D0/RX_2") (pintype "unspecified"))
    )
    (net (code "17") (name "D1") (class "Default")
      (node (ref "H5") (pin "1") (pinfunction "1_1") (pintype "unspecified"))
      (node (ref "J2") (pin "1") (pinfunction "D1/TX_1") (pintype "unspecified"))
    )
    (net (code "18") (name "D2") (class "Default")
      (node (ref "H5") (pin "5") (pinfunction "5_5") (pintype "unspecified"))
      (node (ref "J2") (pin "5") (pinfunction "D2/INT0_5") (pintype "unspecified"))
      (node (ref "SENS_2") (pin "2") (pinfunction "2_2") (pintype "unspecified"))
      (node (ref "SW2") (pin "1") (pinfunction "1_1") (pintype "unspecified"))
      (node (ref "SW2") (pin "2") (pinfunction "2_2") (pintype "unspecified"))
    )
    (net (code "19") (name "D3") (class "Default")
      (node (ref "H5") (pin "6") (pinfunction "6_6") (pintype "unspecified"))
      (node (ref "J2") (pin "6") (pinfunction "D3/INT1_6") (pintype "unspecified"))
      (node (ref "SENS_3") (pin "2") (pinfunction "2_2") (pintype "unspecified"))
      (node (ref "SW3") (pin "1") (pinfunction "1_1") (pintype "unspecified"))
      (node (ref "SW3") (pin "2") (pinfunction "2_2") (pintype "unspecified"))
    )
    (net (code "20") (name "D4") (class "Default")
      (node (ref "ALD") (pin "1") (pinfunction "A_1") (pintype "input"))
      (node (ref "AQ") (pin "1") (pinfunction "G_1") (pintype "unspecified"))
      (node (ref "ARG") (pin "2") (pinfunction "2_2") (pintype "input"))
      (node (ref "H5") (pin "7") (pinfunction "7_7") (pintype "unspecified"))
      (node (ref "J2") (pin "7") (pinfunction "D4/T0_7") (pintype "unspecified"))
      (node (ref "OUT_4") (pin "1") (pinfunction "1_1") (pintype "unspecified"))
    )
    (net (code "21") (name "D5") (class "Default")
      (node (ref "BLD") (pin "1") (pinfunction "A_1") (pintype "input"))
      (node (ref "BQ") (pin "1") (pinfunction "G_1") (pintype "unspecified"))
      (node (ref "BRG") (pin "2") (pinfunction "2_2") (pintype "input"))
      (node (ref "H5") (pin "8") (pinfunction "8_8") (pintype "unspecified"))
      (node (ref "J2") (pin "8") (pinfunction "D5/T1_8") (pintype "unspecified"))
      (node (ref "OUT_5") (pin "1") (pinfunction "1_1") (pintype "unspecified"))
    )
    (net (code "22") (name "D6") (class "Default")
      (node (ref "CLD") (pin "1") (pinfunction "A_1") (pintype "input"))
      (node (ref "CQ") (pin "1") (pinfunction "G_1") (pintype "unspecified"))
      (node (ref "CRG") (pin "2") (pinfunction "2_2") (pintype "input"))
      (node (ref "H5") (pin "9") (pinfunction "9_9") (pintype "unspecified"))
      (node (ref "J2") (pin "9") (pinfunction "D6/AIN0_9") (pintype "unspecified"))
      (node (ref "OUT_6") (pin "1") (pinfunction "1_1") (pintype "unspecified"))
    )
    (net (code "23") (name "D7") (class "Default")
      (node (ref "DLD") (pin "1") (pinfunction "A_1") (pintype "input"))
      (node (ref "DQ") (pin "1") (pinfunction "G_1") (pintype "unspecified"))
      (node (ref "DRG") (pin "2") (pinfunction "2_2") (pintype "input"))
      (node (ref "H5") (pin "10") (pinfunction "10_10") (pintype "unspecified"))
      (node (ref "J2") (pin "10") (pinfunction "D7/AIN1_10") (pintype "unspecified"))
      (node (ref "OUT_7") (pin "1") (pinfunction "1_1") (pintype "unspecified"))
    )
    (net (code "24") (name "D8") (class "Default")
      (node (ref "ELD") (pin "1") (pinfunction "A_1") (pintype "input"))
      (node (ref "EQ") (pin "1") (pinfunction "G_1") (pintype "unspecified"))
      (node (ref "ERG") (pin "2") (pinfunction "2_2") (pintype "input"))
      (node (ref "H5") (pin "11") (pinfunction "11_11") (pintype "unspecified"))
      (node (ref "J2") (pin "11") (pinfunction "D8/ICP_11") (pintype "unspecified"))
      (node (ref "OUT_8") (pin "1") (pinfunction "1_1") (pintype "unspecified"))
    )
    (net (code "25") (name "D9") (class "Default")
      (node (ref "FLD") (pin "1") (pinfunction "A_1") (pintype "input"))
      (node (ref "FQ") (pin "1") (pinfunction "G_1") (pintype "unspecified"))
      (node (ref "FRG") (pin "2") (pinfunction "2_2") (pintype "input"))
      (node (ref "H5") (pin "12") (pinfunction "12_12") (pintype "unspecified"))
      (node (ref "J2") (pin "12") (pinfunction "D9/0C1_12") (pintype "unspecified"))
      (node (ref "OUT_9") (pin "1") (pinfunction "1_1") (pintype "unspecified"))
    )
    (net (code "26") (name "D10") (class "Default")
      (node (ref "GLD") (pin "1") (pinfunction "A_1") (pintype "input"))
      (node (ref "GQ") (pin "1") (pinfunction "G_1") (pintype "unspecified"))
      (node (ref "GRG") (pin "2") (pinfunction "2_2") (pintype "input"))
      (node (ref "H5") (pin "13") (pinfunction "13_13") (pintype "unspecified"))
      (node (ref "J2") (pin "13") (pinfunction "D10_13") (pintype "unspecified"))
      (node (ref "OUT_10") (pin "1") (pinfunction "1_1") (pintype "unspecified"))
    )
    (net (code "27") (name "D11") (class "Default")
      (node (ref "H5") (pin "14") (pinfunction "14_14") (pintype "unspecified"))
      (node (ref "HLD") (pin "1") (pinfunction "A_1") (pintype "input"))
      (node (ref "HQ") (pin "1") (pinfunction "G_1") (pintype "unspecified"))
      (node (ref "HRG") (pin "2") (pinfunction "2_2") (pintype "input"))
      (node (ref "J2") (pin "14") (pinfunction "D11/MOSI_14") (pintype "unspecified"))
      (node (ref "OUT_11") (pin "1") (pinfunction "1_1") (pintype "unspecified"))
    )
    (net (code "28") (name "D13") (class "Default")
      (node (ref "H4") (pin "15") (pinfunction "15_15") (pintype "unspecified"))
      (node (ref "J2") (pin "16") (pinfunction "SCK/D13_16") (pintype "unspecified"))
    )
    (net (code "29") (name "GND") (class "Default")
      (node (ref "AQ") (pin "2") (pinfunction "S_2") (pintype "unspecified"))
      (node (ref "ARG") (pin "1") (pinfunction "1_1") (pintype "input"))
      (node (ref "ARL") (pin "1") (pinfunction "1_1") (pintype "input"))
      (node (ref "BQ") (pin "2") (pinfunction "S_2") (pintype "unspecified"))
      (node (ref "BRG") (pin "1") (pinfunction "1_1") (pintype "input"))
      (node (ref "BRL") (pin "1") (pinfunction "1_1") (pintype "input"))
      (node (ref "BUZZER1") (pin "2") (pinfunction "2_2") (pintype "unspecified"))
      (node (ref "C1") (pin "2") (pinfunction "2_2") (pintype "input"))
      (node (ref "C10") (pin "1") (pinfunction "1_1") (pintype "unspecified"))
      (node (ref "C11") (pin "1") (pinfunction "1_1") (pintype "unspecified"))
      (node (ref "C2") (pin "2") (pinfunction "2_2") (pintype "input"))
      (node (ref "CQ") (pin "2") (pinfunction "S_2") (pintype "unspecified"))
      (node (ref "CRG") (pin "1") (pinfunction "1_1") (pintype "input"))
      (node (ref "CRL") (pin "1") (pinfunction "1_1") (pintype "input"))
      (node (ref "DC1") (pin "2") (pinfunction "2_2") (pintype "unspecified"))
      (node (ref "DC1") (pin "3") (pinfunction "3_3") (pintype "unspecified"))
      (node (ref "DQ") (pin "2") (pinfunction "S_2") (pintype "unspecified"))
      (node (ref "DRG") (pin "1") (pinfunction "1_1") (pintype "input"))
      (node (ref "DRL") (pin "1") (pinfunction "1_1") (pintype "input"))
      (node (ref "EQ") (pin "2") (pinfunction "S_2") (pintype "unspecified"))
      (node (ref "ERG") (pin "1") (pinfunction "1_1") (pintype "input"))
      (node (ref "ERL") (pin "1") (pinfunction "1_1") (pintype "input"))
      (node (ref "EX_V") (pin "2") (pinfunction "2_2") (pintype "unspecified"))
      (node (ref "FQ") (pin "2") (pinfunction "S_2") (pintype "unspecified"))
      (node (ref "FRG") (pin "1") (pinfunction "1_1") (pintype "input"))
      (node (ref "FRL") (pin "1") (pinfunction "1_1") (pintype "input"))
      (node (ref "GQ") (pin "2") (pinfunction "S_2") (pintype "unspecified"))
      (node (ref "GRG") (pin "1") (pinfunction "1_1") (pintype "input"))
      (node (ref "GRL") (pin "1") (pinfunction "1_1") (pintype "input"))
      (node (ref "H1") (pin "6") (pinfunction "6_6") (pintype "input"))
      (node (ref "H11") (pin "6") (pinfunction "6_6") (pintype "input"))
      (node (ref "H2") (pin "6") (pinfunction "6_6") (pintype "input"))
      (node (ref "H3") (pin "6") (pinfunction "6_6") (pintype "input"))
      (node (ref "H4") (pin "2") (pinfunction "2_2") (pintype "unspecified"))
      (node (ref "H5") (pin "4") (pinfunction "4_4") (pintype "unspecified"))
      (node (ref "H6") (pin "6") (pinfunction "6_6") (pintype "input"))
      (node (ref "HQ") (pin "2") (pinfunction "S_2") (pintype "unspecified"))
      (node (ref "HRG") (pin "1") (pinfunction "1_1") (pintype "input"))
      (node (ref "HRL") (pin "1") (pinfunction "1_1") (pintype "input"))
      (node (ref "J2") (pin "29") (pinfunction "GND_29") (pintype "unspecified"))
      (node (ref "J2") (pin "4") (pinfunction "GND_4") (pintype "unspecified"))
      (node (ref "OLED") (pin "2") (pinfunction "GND_2") (pintype "passive"))
      (node (ref "OUT_10") (pin "2") (pinfunction "2_2") (pintype "unspecified"))
      (node (ref "OUT_11") (pin "2") (pinfunction "2_2") (pintype "unspecified"))
      (node (ref "OUT_4") (pin "2") (pinfunction "2_2") (pintype "unspecified"))
      (node (ref "OUT_5") (pin "2") (pinfunction "2_2") (pintype "unspecified"))
      (node (ref "OUT_6") (pin "2") (pinfunction "2_2") (pintype "unspecified"))
      (node (ref "OUT_7") (pin "2") (pinfunction "2_2") (pintype "unspecified"))
      (node (ref "OUT_8") (pin "2") (pinfunction "2_2") (pintype "unspecified"))
      (node (ref "OUT_9") (pin "2") (pinfunction "2_2") (pintype "unspecified"))
      (node (ref "P2") (pin "1") (pinfunction "1_1") (pintype "input"))
      (node (ref "P3") (pin "1") (pinfunction "1_1") (pintype "input"))
      (node (ref "RL12V") (pin "2") (pinfunction "2_2") (pintype "input"))
      (node (ref "RL5VB") (pin "2") (pinfunction "2_2") (pintype "input"))
      (node (ref "SENS_2") (pin "3") (pinfunction "3_3") (pintype "unspecified"))
      (node (ref "SENS_3") (pin "3") (pinfunction "3_3") (pintype "unspecified"))
      (node (ref "SENS_A0") (pin "3") (pinfunction "3_3") (pintype "unspecified"))
      (node (ref "SENS_A1") (pin "3") (pinfunction "3_3") (pintype "unspecified"))
      (node (ref "SENS_A2") (pin "3") (pinfunction "3_3") (pintype "unspecified"))
      (node (ref "SENS_A3") (pin "3") (pinfunction "3_3") (pintype "unspecified"))
      (node (ref "SW2") (pin "3") (pinfunction "3_3") (pintype "unspecified"))
      (node (ref "SW2") (pin "4") (pinfunction "4_4") (pintype "unspecified"))
      (node (ref "SW3") (pin "3") (pinfunction "3_3") (pintype "unspecified"))
      (node (ref "SW3") (pin "4") (pinfunction "4_4") (pintype "unspecified"))
      (node (ref "SWA0") (pin "3") (pinfunction "3_3") (pintype "unspecified"))
      (node (ref "SWA0") (pin "4") (pinfunction "4_4") (pintype "unspecified"))
      (node (ref "SWA1") (pin "3") (pinfunction "3_3") (pintype "unspecified"))
      (node (ref "SWA1") (pin "4") (pinfunction "4_4") (pintype "unspecified"))
      (node (ref "SWA2") (pin "3") (pinfunction "3_3") (pintype "unspecified"))
      (node (ref "SWA2") (pin "4") (pinfunction "4_4") (pintype "unspecified"))
      (node (ref "SWA3") (pin "3") (pinfunction "3_3") (pintype "unspecified"))
      (node (ref "SWA3") (pin "4") (pinfunction "4_4") (pintype "unspecified"))
      (node (ref "U3") (pin "3") (pinfunction "GND_3") (pintype "unspecified"))
      (node (ref "U5") (pin "2") (pinfunction "GND_2") (pintype "unspecified"))
    )
    (net (code "30") (name "Net-(ADM-A)") (class "Default")
      (node (ref "ACM") (pin "2") (pinfunction "2_2") (pintype "input"))
      (node (ref "ACON") (pin "2") (pinfunction "2_2") (pintype "unspecified"))
      (node (ref "ADM") (pin "2") (pinfunction "A_2") (pintype "unspecified"))
      (node (ref "AQ") (pin "3") (pinfunction "D_3") (pintype "unspecified"))
    )
    (net (code "31") (name "Net-(ADM-C)") (class "Default")
      (node (ref "ACM") (pin "1") (pinfunction "1_1") (pintype "input"))
      (node (ref "ACON") (pin "1") (pinfunction "1_1") (pintype "unspecified"))
      (node (ref "ADM") (pin "1") (pinfunction "C_1") (pintype "unspecified"))
      (node (ref "AJ12V") (pin "1") (pinfunction "1_1") (pintype "bidirectional"))
      (node (ref "AJ5V") (pin "1") (pinfunction "1_1") (pintype "bidirectional"))
    )
    (net (code "32") (name "Net-(ALD-C)") (class "Default")
      (node (ref "ALD") (pin "2") (pinfunction "C_2") (pintype "input"))
      (node (ref "ARL") (pin "2") (pinfunction "2_2") (pintype "input"))
    )
    (net (code "33") (name "Net-(BDM-A)") (class "Default")
      (node (ref "BCM") (pin "2") (pinfunction "2_2") (pintype "input"))
      (node (ref "BCON") (pin "2") (pinfunction "2_2") (pintype "unspecified"))
      (node (ref "BDM") (pin "2") (pinfunction "A_2") (pintype "unspecified"))
      (node (ref "BQ") (pin "3") (pinfunction "D_3") (pintype "unspecified"))
    )
    (net (code "34") (name "Net-(BDM-C)") (class "Default")
      (node (ref "BCM") (pin "1") (pinfunction "1_1") (pintype "input"))
      (node (ref "BCON") (pin "1") (pinfunction "1_1") (pintype "unspecified"))
      (node (ref "BDM") (pin "1") (pinfunction "C_1") (pintype "unspecified"))
      (node (ref "BJ12V") (pin "1") (pinfunction "1_1") (pintype "bidirectional"))
      (node (ref "BJ5V") (pin "1") (pinfunction "1_1") (pintype "bidirectional"))
    )
    (net (code "35") (name "Net-(BLD-C)") (class "Default")
      (node (ref "BLD") (pin "2") (pinfunction "C_2") (pintype "input"))
      (node (ref "BRL") (pin "2") (pinfunction "2_2") (pintype "input"))
    )
    (net (code "36") (name "Net-(CDM-A)") (class "Default")
      (node (ref "CCM") (pin "2") (pinfunction "2_2") (pintype "input"))
      (node (ref "CCON") (pin "2") (pinfunction "2_2") (pintype "unspecified"))
      (node (ref "CDM") (pin "2") (pinfunction "A_2") (pintype "unspecified"))
      (node (ref "CQ") (pin "3") (pinfunction "D_3") (pintype "unspecified"))
    )
    (net (code "37") (name "Net-(CDM-C)") (class "Default")
      (node (ref "CCM") (pin "1") (pinfunction "1_1") (pintype "input"))
      (node (ref "CCON") (pin "1") (pinfunction "1_1") (pintype "unspecified"))
      (node (ref "CDM") (pin "1") (pinfunction "C_1") (pintype "unspecified"))
      (node (ref "CJ12V") (pin "1") (pinfunction "1_1") (pintype "bidirectional"))
      (node (ref "CJ5V") (pin "1") (pinfunction "1_1") (pintype "bidirectional"))
    )
    (net (code "38") (name "Net-(CLD-C)") (class "Default")
      (node (ref "CLD") (pin "2") (pinfunction "C_2") (pintype "input"))
      (node (ref "CRL") (pin "2") (pinfunction "2_2") (pintype "input"))
    )
    (net (code "39") (name "Net-(DDM-A)") (class "Default")
      (node (ref "DCM") (pin "2") (pinfunction "2_2") (pintype "input"))
      (node (ref "DCON") (pin "2") (pinfunction "2_2") (pintype "unspecified"))
      (node (ref "DDM") (pin "2") (pinfunction "A_2") (pintype "unspecified"))
      (node (ref "DQ") (pin "3") (pinfunction "D_3") (pintype "unspecified"))
    )
    (net (code "40") (name "Net-(DDM-C)") (class "Default")
      (node (ref "DCM") (pin "1") (pinfunction "1_1") (pintype "input"))
      (node (ref "DCON") (pin "1") (pinfunction "1_1") (pintype "unspecified"))
      (node (ref "DDM") (pin "1") (pinfunction "C_1") (pintype "unspecified"))
      (node (ref "DJ12V") (pin "1") (pinfunction "1_1") (pintype "bidirectional"))
      (node (ref "DJ5V") (pin "1") (pinfunction "1_1") (pintype "bidirectional"))
    )
    (net (code "41") (name "Net-(DLD-C)") (class "Default")
      (node (ref "DLD") (pin "2") (pinfunction "C_2") (pintype "input"))
      (node (ref "DRL") (pin "2") (pinfunction "2_2") (pintype "input"))
    )
    (net (code "42") (name "Net-(EDM-A)") (class "Default")
      (node (ref "ECM") (pin "2") (pinfunction "2_2") (pintype "input"))
      (node (ref "ECON") (pin "2") (pinfunction "2_2") (pintype "unspecified"))
      (node (ref "EDM") (pin "2") (pinfunction "A_2") (pintype "unspecified"))
      (node (ref "EQ") (pin "3") (pinfunction "D_3") (pintype "unspecified"))
    )
    (net (code "43") (name "Net-(EDM-C)") (class "Default")
      (node (ref "ECM") (pin "1") (pinfunction "1_1") (pintype "input"))
      (node (ref "ECON") (pin "1") (pinfunction "1_1") (pintype "unspecified"))
      (node (ref "EDM") (pin "1") (pinfunction "C_1") (pintype "unspecified"))
      (node (ref "EJ12V") (pin "1") (pinfunction "1_1") (pintype "bidirectional"))
      (node (ref "EJ5V") (pin "1") (pinfunction "1_1") (pintype "bidirectional"))
    )
    (net (code "44") (name "Net-(ELD-C)") (class "Default")
      (node (ref "ELD") (pin "2") (pinfunction "C_2") (pintype "input"))
      (node (ref "ERL") (pin "2") (pinfunction "2_2") (pintype "input"))
    )
    (net (code "45") (name "Net-(FDM-A)") (class "Default")
      (node (ref "FCM") (pin "2") (pinfunction "2_2") (pintype "input"))
      (node (ref "FCON") (pin "2") (pinfunction "2_2") (pintype "unspecified"))
      (node (ref "FDM") (pin "2") (pinfunction "A_2") (pintype "unspecified"))
      (node (ref "FQ") (pin "3") (pinfunction "D_3") (pintype "unspecified"))
    )
    (net (code "46") (name "Net-(FDM-C)") (class "Default")
      (node (ref "FCM") (pin "1") (pinfunction "1_1") (pintype "input"))
      (node (ref "FCON") (pin "1") (pinfunction "1_1") (pintype "unspecified"))
      (node (ref "FDM") (pin "1") (pinfunction "C_1") (pintype "unspecified"))
      (node (ref "FJ12V") (pin "1") (pinfunction "1_1") (pintype "bidirectional"))
      (node (ref "FJ5V") (pin "1") (pinfunction "1_1") (pintype "bidirectional"))
    )
    (net (code "47") (name "Net-(FLD-C)") (class "Default")
      (node (ref "FLD") (pin "2") (pinfunction "C_2") (pintype "input"))
      (node (ref "FRL") (pin "2") (pinfunction "2_2") (pintype "input"))
    )
    (net (code "48") (name "Net-(GDM-A)") (class "Default")
      (node (ref "GCM") (pin "2") (pinfunction "2_2") (pintype "input"))
      (node (ref "GCON") (pin "2") (pinfunction "2_2") (pintype "unspecified"))
      (node (ref "GDM") (pin "2") (pinfunction "A_2") (pintype "unspecified"))
      (node (ref "GQ") (pin "3") (pinfunction "D_3") (pintype "unspecified"))
    )
    (net (code "49") (name "Net-(GDM-C)") (class "Default")
      (node (ref "GCM") (pin "1") (pinfunction "1_1") (pintype "input"))
      (node (ref "GCON") (pin "1") (pinfunction "1_1") (pintype "unspecified"))
      (node (ref "GDM") (pin "1") (pinfunction "C_1") (pintype "unspecified"))
      (node (ref "GJ12V") (pin "1") (pinfunction "1_1") (pintype "bidirectional"))
      (node (ref "GJ5V") (pin "1") (pinfunction "1_1") (pintype "bidirectional"))
    )
    (net (code "50") (name "Net-(GLD-C)") (class "Default")
      (node (ref "GLD") (pin "2") (pinfunction "C_2") (pintype "input"))
      (node (ref "GRL") (pin "2") (pinfunction "2_2") (pintype "input"))
    )
    (net (code "51") (name "Net-(H4-Pad3)") (class "Default")
      (node (ref "H4") (pin "3") (pinfunction "3_3") (pintype "unspecified"))
      (node (ref "J2") (pin "28") (pinfunction "RESET_28") (pintype "unspecified"))
    )
    (net (code "52") (name "Net-(H5-Pad3)") (class "Default")
      (node (ref "H5") (pin "3") (pinfunction "3_3") (pintype "unspecified"))
      (node (ref "J2") (pin "3") (pinfunction "RESET_3") (pintype "unspecified"))
    )
    (net (code "53") (name "Net-(HDM-A)") (class "Default")
      (node (ref "HCM") (pin "2") (pinfunction "2_2") (pintype "input"))
      (node (ref "HCON") (pin "2") (pinfunction "2_2") (pintype "unspecified"))
      (node (ref "HDM") (pin "2") (pinfunction "A_2") (pintype "unspecified"))
      (node (ref "HQ") (pin "3") (pinfunction "D_3") (pintype "unspecified"))
    )
    (net (code "54") (name "Net-(HDM-C)") (class "Default")
      (node (ref "HCM") (pin "1") (pinfunction "1_1") (pintype "input"))
      (node (ref "HCON") (pin "1") (pinfunction "1_1") (pintype "unspecified"))
      (node (ref "HDM") (pin "1") (pinfunction "C_1") (pintype "unspecified"))
      (node (ref "HJ12V") (pin "1") (pinfunction "1_1") (pintype "bidirectional"))
      (node (ref "HJ5V") (pin "1") (pinfunction "1_1") (pintype "bidirectional"))
    )
    (net (code "55") (name "Net-(HLD-C)") (class "Default")
      (node (ref "HLD") (pin "2") (pinfunction "C_2") (pintype "input"))
      (node (ref "HRL") (pin "2") (pinfunction "2_2") (pintype "input"))
    )
    (net (code "56") (name "Net-(J2-AREF)") (class "Default")
      (node (ref "H4") (pin "13") (pinfunction "13_13") (pintype "unspecified"))
      (node (ref "J2") (pin "18") (pinfunction "AREF_18") (pintype "unspecified"))
    )
    (net (code "57") (name "Net-(L12V-C)") (class "Default")
      (node (ref "L12V") (pin "2") (pinfunction "C_2") (pintype "input"))
      (node (ref "RL12V") (pin "1") (pinfunction "1_1") (pintype "input"))
    )
    (net (code "58") (name "Net-(LVB-C)") (class "Default")
      (node (ref "LVB") (pin "2") (pinfunction "C_2") (pintype "input"))
      (node (ref "RL5VB") (pin "1") (pinfunction "1_1") (pintype "input"))
    )
    (net (code "59") (name "Net-(U3-EN)") (class "Default")
      (node (ref "R1") (pin "1") (pinfunction "1_1") (pintype "input"))
      (node (ref "U3") (pin "1") (pinfunction "EN_1") (pintype "unspecified"))
    )
    (net (code "61") (name "unconnected-(H1-Pad2)") (class "Default")
      (node (ref "H1") (pin "2") (pinfunction "2_2") (pintype "input"))
    )
    (net (code "62") (name "unconnected-(H1-Pad3)") (class "Default")
      (node (ref "H1") (pin "3") (pinfunction "3_3") (pintype "input"))
    )
    (net (code "63") (name "unconnected-(H1-Pad4)") (class "Default")
      (node (ref "H1") (pin "4") (pinfunction "4_4") (pintype "input"))
    )
    (net (code "64") (name "unconnected-(H1-Pad5)") (class "Default")
      (node (ref "H1") (pin "5") (pinfunction "5_5") (pintype "input"))
    )
    (net (code "65") (name "unconnected-(H2-Pad2)") (class "Default")
      (node (ref "H2") (pin "2") (pinfunction "2_2") (pintype "input"))
    )
    (net (code "66") (name "unconnected-(H2-Pad3)") (class "Default")
      (node (ref "H2") (pin "3") (pinfunction "3_3") (pintype "input"))
    )
    (net (code "67") (name "unconnected-(H2-Pad4)") (class "Default")
      (node (ref "H2") (pin "4") (pinfunction "4_4") (pintype "input"))
    )
    (net (code "68") (name "unconnected-(H2-Pad5)") (class "Default")
      (node (ref "H2") (pin "5") (pinfunction "5_5") (pintype "input"))
    )
    (net (code "69") (name "unconnected-(H3-Pad2)") (class "Default")
      (node (ref "H3") (pin "2") (pinfunction "2_2") (pintype "input"))
    )
    (net (code "70") (name "unconnected-(H3-Pad3)") (class "Default")
      (node (ref "H3") (pin "3") (pinfunction "3_3") (pintype "input"))
    )
    (net (code "71") (name "unconnected-(H3-Pad4)") (class "Default")
      (node (ref "H3") (pin "4") (pinfunction "4_4") (pintype "input"))
    )
    (net (code "72") (name "unconnected-(H3-Pad5)") (class "Default")
      (node (ref "H3") (pin "5") (pinfunction "5_5") (pintype "input"))
    )
    (net (code "73") (name "unconnected-(H6-Pad2)") (class "Default")
      (node (ref "H6") (pin "2") (pinfunction "2_2") (pintype "input"))
    )
    (net (code "74") (name "unconnected-(H6-Pad3)") (class "Default")
      (node (ref "H6") (pin "3") (pinfunction "3_3") (pintype "input"))
    )
    (net (code "75") (name "unconnected-(H6-Pad4)") (class "Default")
      (node (ref "H6") (pin "4") (pinfunction "4_4") (pintype "input"))
    )
    (net (code "76") (name "unconnected-(H6-Pad5)") (class "Default")
      (node (ref "H6") (pin "5") (pinfunction "5_5") (pintype "input"))
    )
    (net (code "77") (name "unconnected-(H11-Pad2)") (class "Default")
      (node (ref "H11") (pin "2") (pinfunction "2_2") (pintype "input"))
    )
    (net (code "78") (name "unconnected-(H11-Pad3)") (class "Default")
      (node (ref "H11") (pin "3") (pinfunction "3_3") (pintype "input"))
    )
    (net (code "79") (name "unconnected-(H11-Pad4)") (class "Default")
      (node (ref "H11") (pin "4") (pinfunction "4_4") (pintype "input"))
    )
    (net (code "80") (name "unconnected-(H11-Pad5)") (class "Default")
      (node (ref "H11") (pin "5") (pinfunction "5_5") (pintype "input"))
    )
    (net (code "81") (name "unconnected-(P2-Pad4)") (class "Default")
      (node (ref "P2") (pin "4") (pinfunction "4_4") (pintype "input"))
    )
    (net (code "82") (name "unconnected-(P2-Pad5)") (class "Default")
      (node (ref "P2") (pin "5") (pinfunction "5_5") (pintype "input"))
    )
    (net (code "83") (name "unconnected-(P3-Pad4)") (class "Default")
      (node (ref "P3") (pin "4") (pinfunction "4_4") (pintype "input"))
    )
    (net (code "84") (name "unconnected-(P3-Pad5)") (class "Default")
      (node (ref "P3") (pin "5") (pinfunction "5_5") (pintype "input"))
    )
  )
)
